# 10MHzRefOsc_2V1.net
KiCad netlist of a schematic drawn in EAGLE
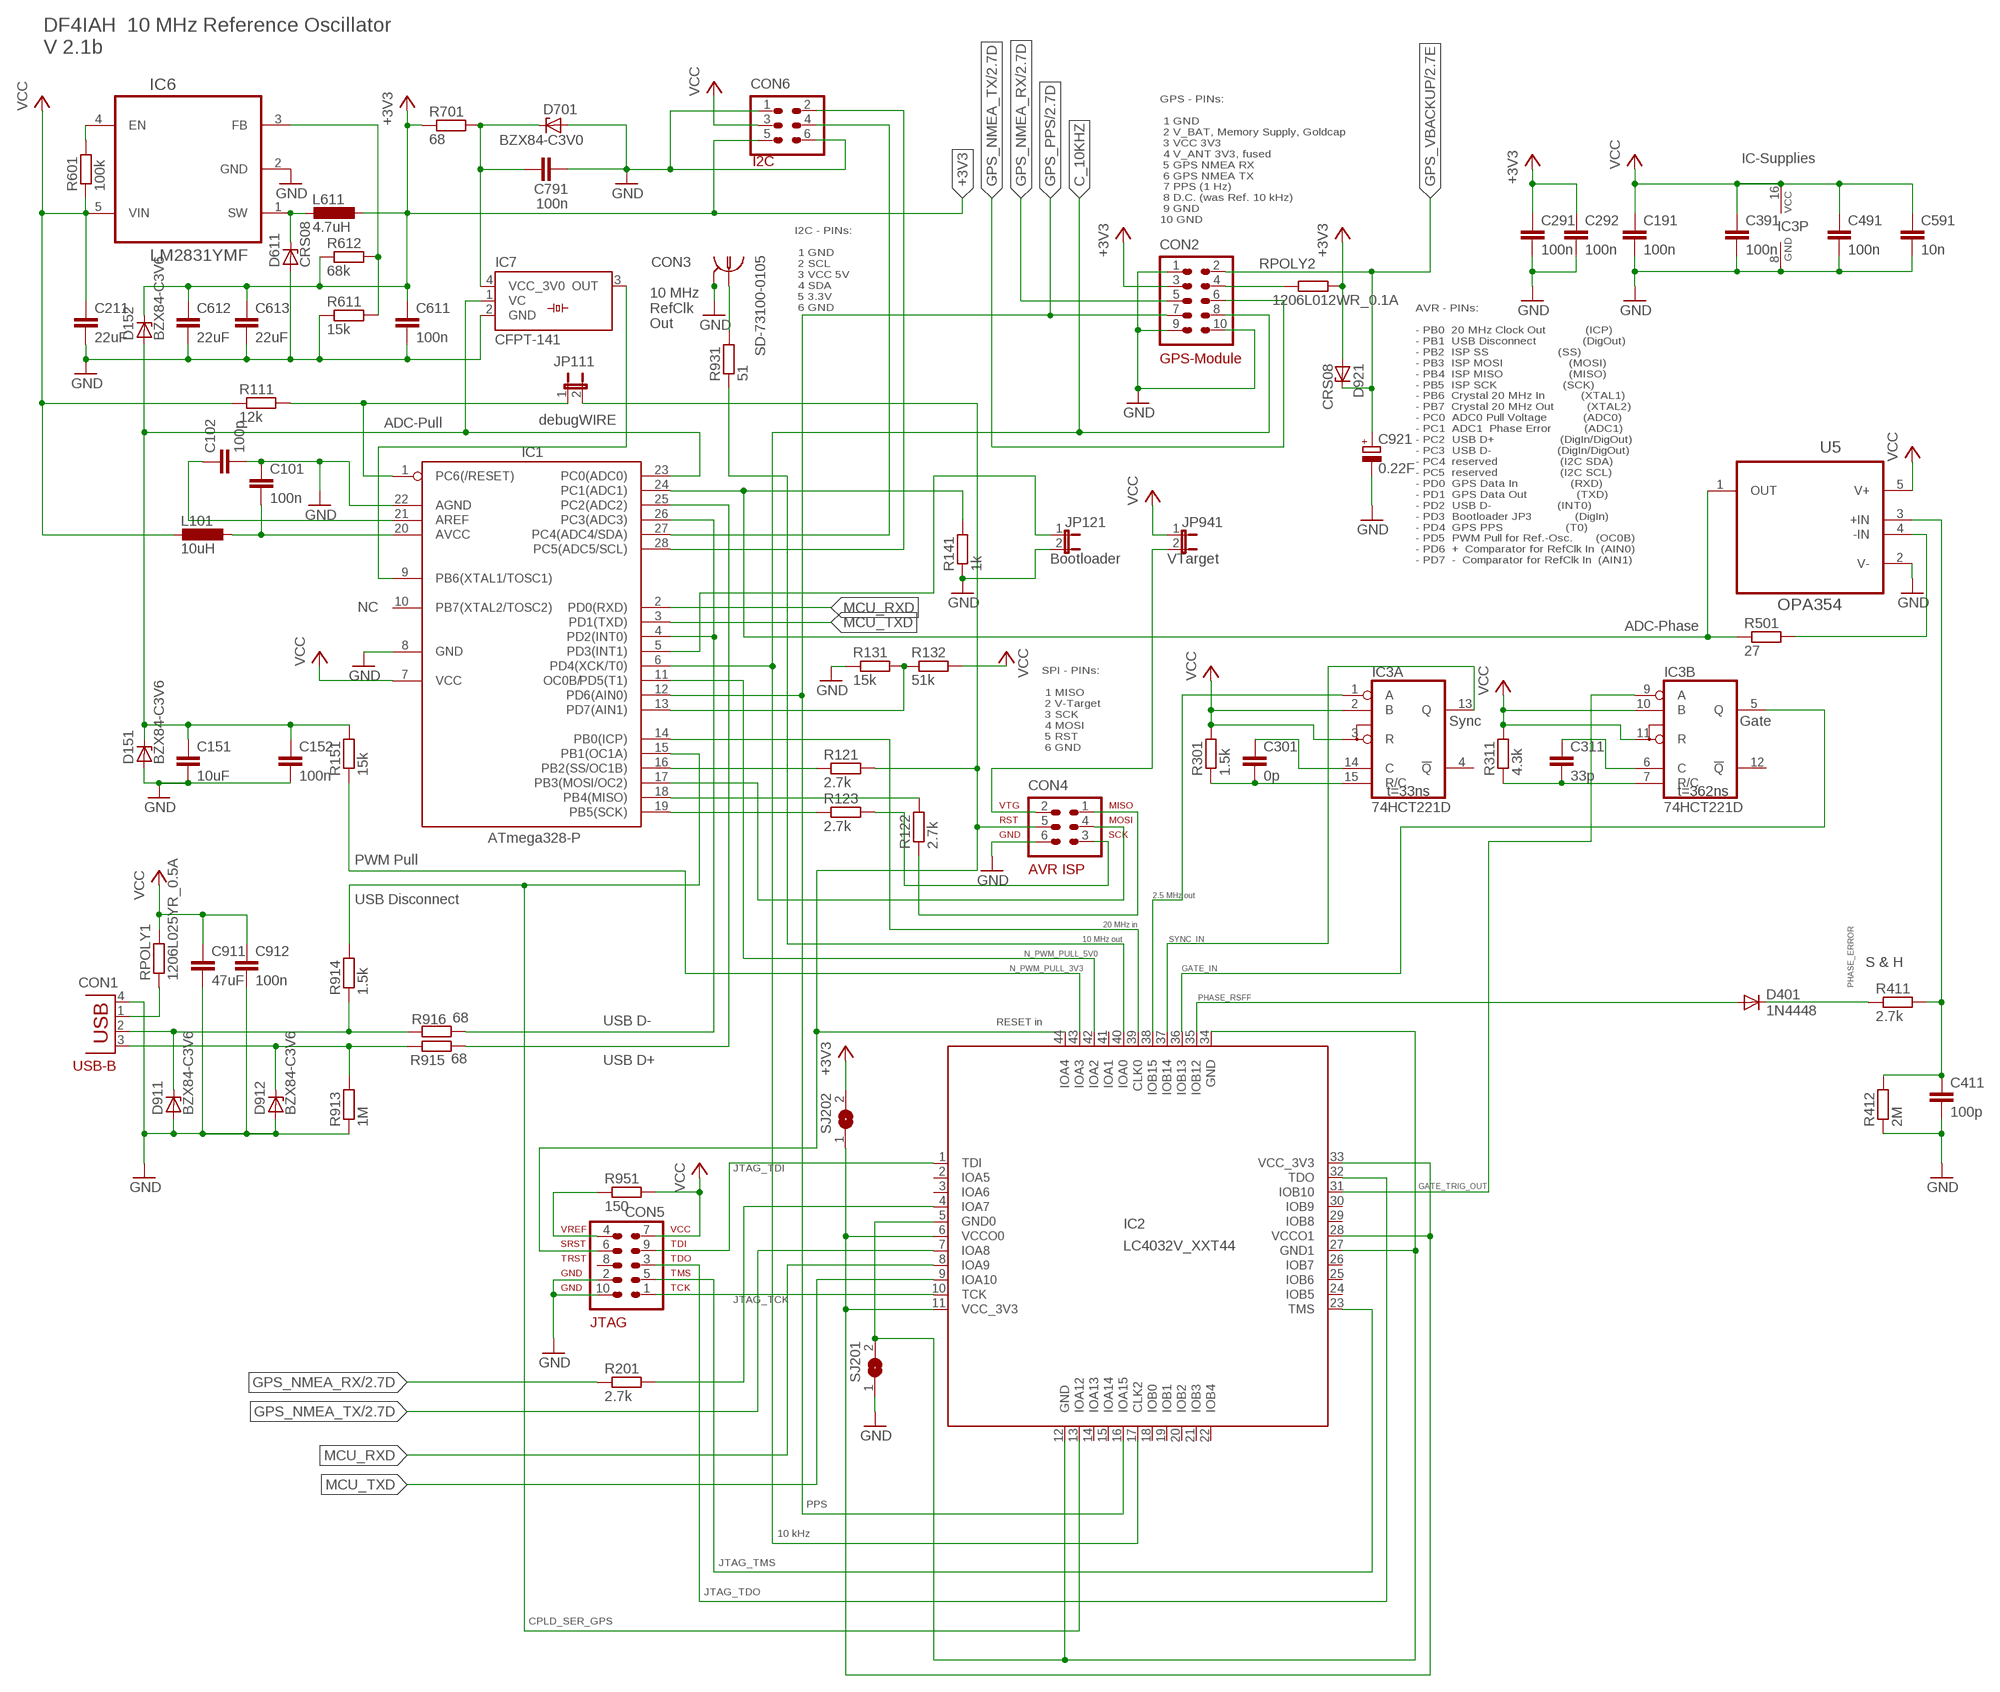
[diagram p0: schematic, sheet 1]
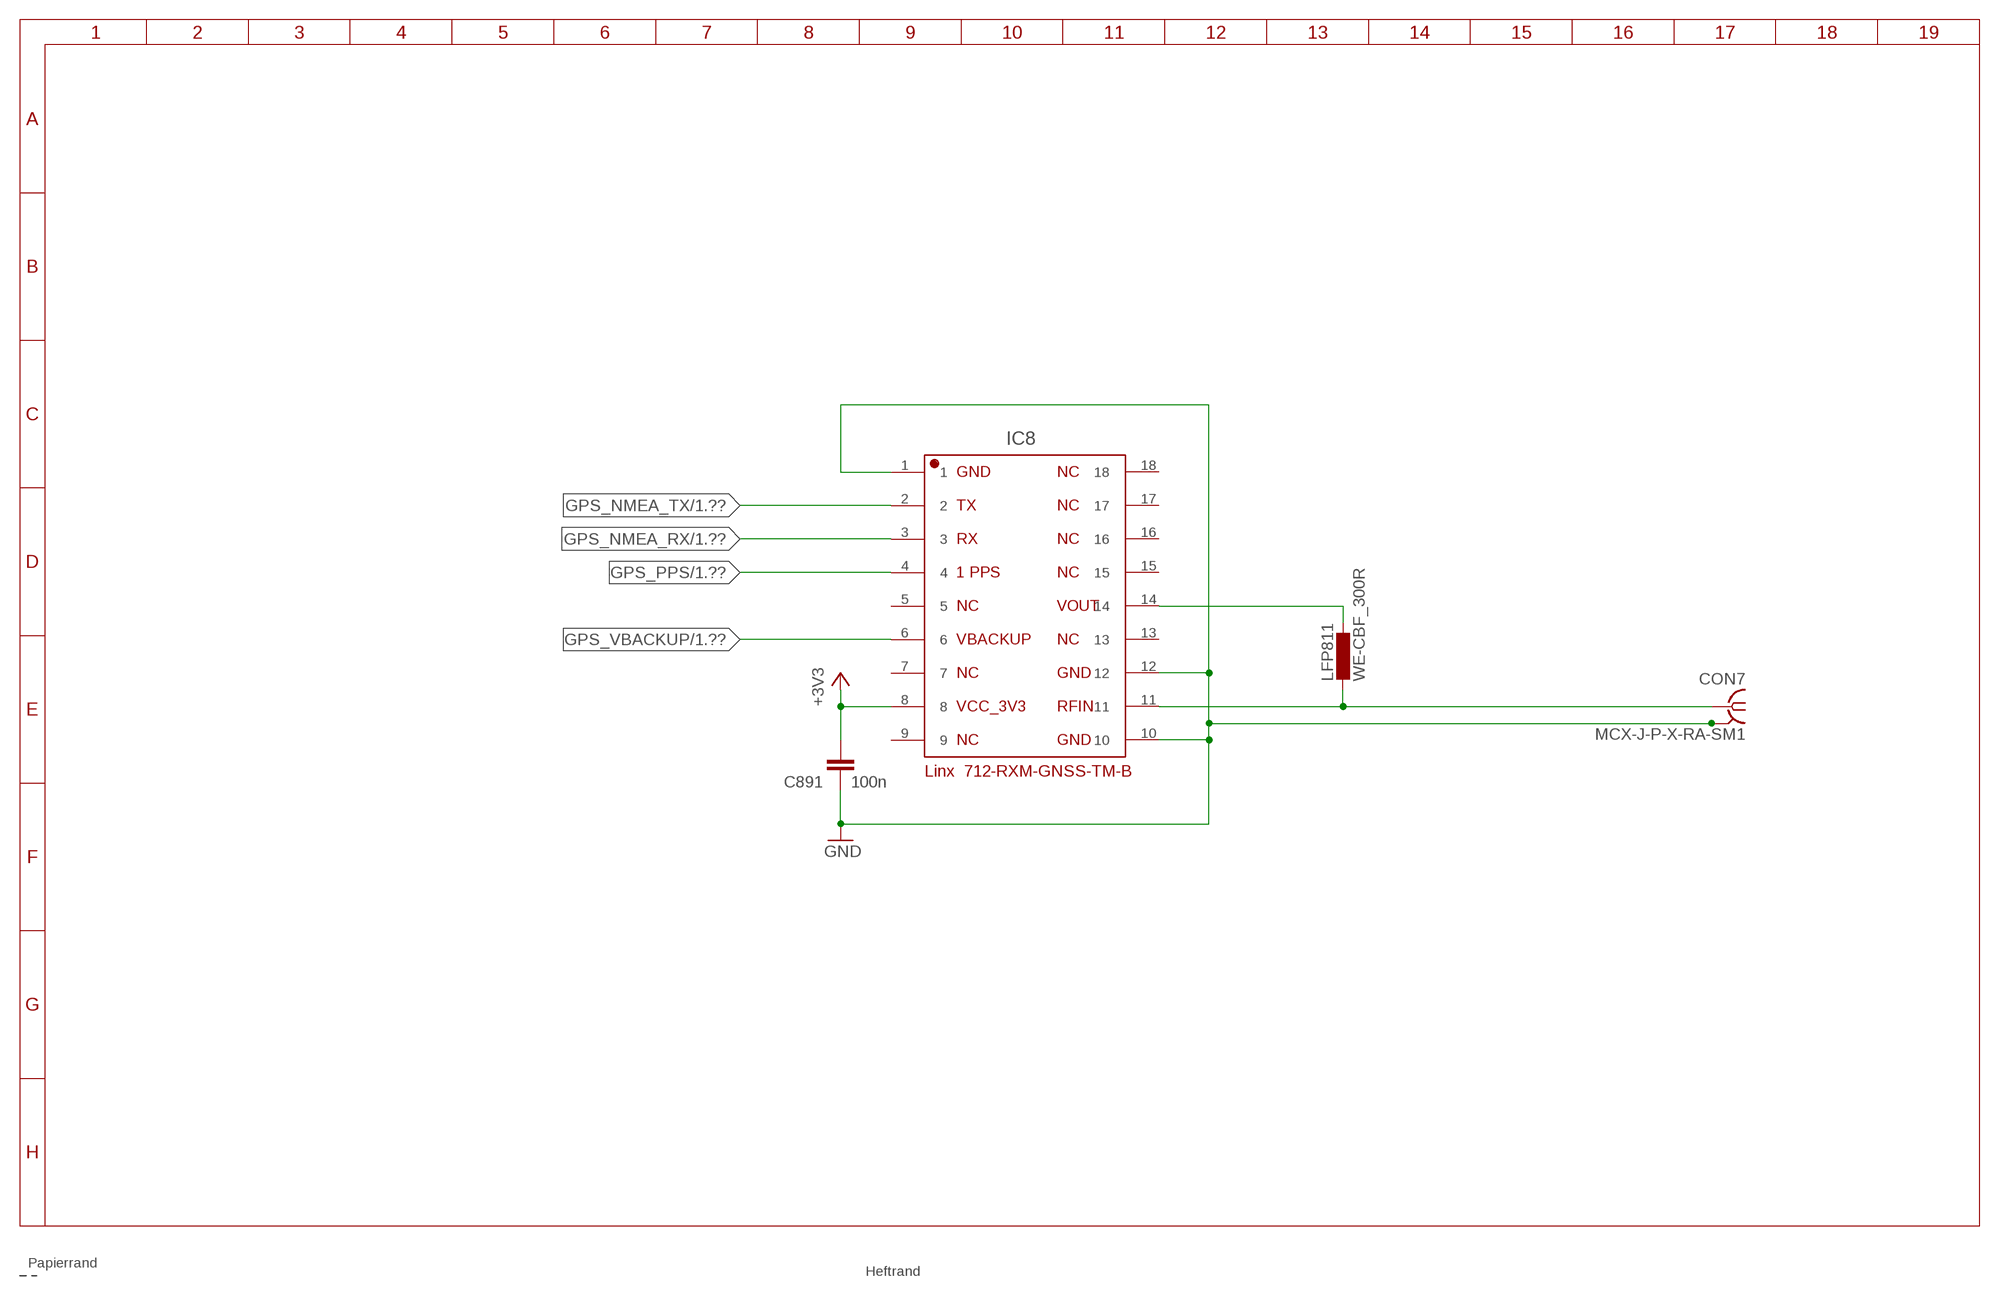
[diagram p1: schematic, sheet 2]
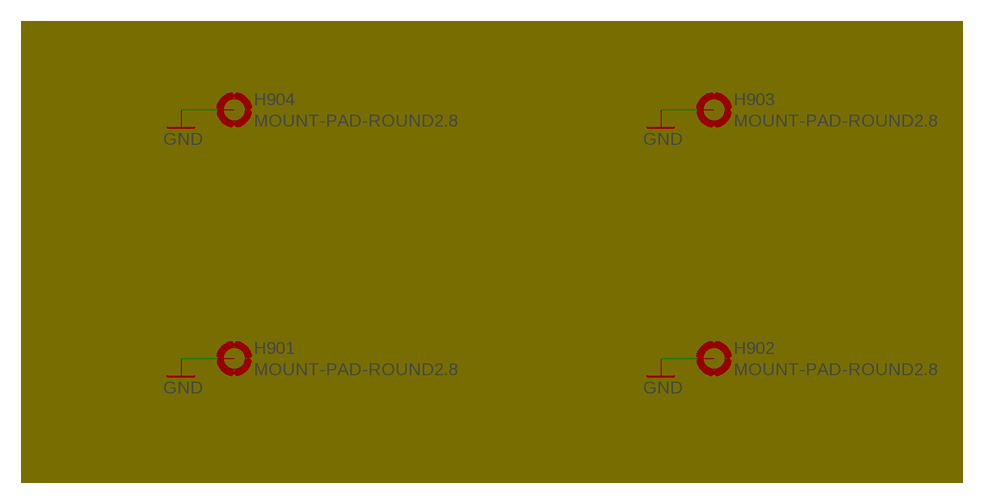
[diagram p2: schematic, sheet 3]

(export (version "E")
  (design (tool "Eeschema 10.0.6"))
  (components
    (comp (ref "C891")
      (value "100n")
      (footprint "eagle-import:C0805")
      (libsource (lib "eagle-import") (part "C-EUC0805"))
    )
    (comp (ref "CON7")
      (value "MCX-J-P-X-RA-SM1")
      (footprint "eagle-import:MCX-J-P-X-RA-SM1")
      (libsource (lib "eagle-import") (part "MCX-J-P-X-RA-SM1"))
    )
    (comp (ref "IC8")
      (value "712-RXM-GNSS-TM-B")
      (footprint "eagle-import:712-RXM-GNSS-TM-B")
      (libsource (lib "eagle-import") (part "712-RXM-GNSS-TM-B"))
    )
    (comp (ref "LFP811")
      (value "WE-CBF_300R")
      (footprint "eagle-import:L3216C")
      (libsource (lib "eagle-import") (part "L-EUL3216C"))
    )
    (comp (ref "C101")
      (value "100n")
      (footprint "eagle-import:C0805")
      (libsource (lib "eagle-import") (part "rcl_C-EUC0805"))
    )
    (comp (ref "C102")
      (value "100p")
      (footprint "eagle-import:C0805")
      (libsource (lib "eagle-import") (part "rcl_C-EUC0805"))
    )
    (comp (ref "C151")
      (value "10uF")
      (footprint "eagle-import:C0805")
      (libsource (lib "eagle-import") (part "rcl_C-EUC0805"))
    )
    (comp (ref "C152")
      (value "100n")
      (footprint "eagle-import:C0805")
      (libsource (lib "eagle-import") (part "rcl_C-EUC0805"))
    )
    (comp (ref "C191")
      (value "100n")
      (footprint "eagle-import:C0805")
      (libsource (lib "eagle-import") (part "rcl_C-EUC0805"))
    )
    (comp (ref "C211")
      (value "22uF")
      (footprint "eagle-import:C0805")
      (libsource (lib "eagle-import") (part "rcl_C-EUC0805"))
    )
    (comp (ref "C291")
      (value "100n")
      (footprint "eagle-import:C0805")
      (libsource (lib "eagle-import") (part "rcl_C-EUC0805"))
    )
    (comp (ref "C292")
      (value "100n")
      (footprint "eagle-import:C0805")
      (libsource (lib "eagle-import") (part "rcl_C-EUC0805"))
    )
    (comp (ref "C301")
      (value "0p")
      (footprint "eagle-import:C0805")
      (libsource (lib "eagle-import") (part "rcl_C-EUC0805"))
    )
    (comp (ref "C311")
      (value "33p")
      (footprint "eagle-import:C0805")
      (libsource (lib "eagle-import") (part "rcl_C-EUC0805"))
    )
    (comp (ref "C391")
      (value "100n")
      (footprint "eagle-import:C0805")
      (libsource (lib "eagle-import") (part "rcl_C-EUC0805"))
    )
    (comp (ref "C411")
      (value "100p")
      (footprint "eagle-import:C0805")
      (libsource (lib "eagle-import") (part "rcl_C-EUC0805"))
    )
    (comp (ref "C491")
      (value "100n")
      (footprint "eagle-import:C0805")
      (libsource (lib "eagle-import") (part "rcl_C-EUC0805"))
    )
    (comp (ref "C591")
      (value "10n")
      (footprint "eagle-import:C0805")
      (libsource (lib "eagle-import") (part "rcl_C-EUC0805"))
    )
    (comp (ref "C611")
      (value "100n")
      (footprint "eagle-import:C0805")
      (libsource (lib "eagle-import") (part "rcl_C-EUC0805"))
    )
    (comp (ref "C612")
      (value "22uF")
      (footprint "eagle-import:C0805")
      (libsource (lib "eagle-import") (part "rcl_C-EUC0805"))
    )
    (comp (ref "C613")
      (value "22uF")
      (footprint "eagle-import:C0805")
      (libsource (lib "eagle-import") (part "rcl_C-EUC0805"))
    )
    (comp (ref "C791")
      (value "100n")
      (footprint "eagle-import:C0805")
      (libsource (lib "eagle-import") (part "rcl_C-EUC0805"))
    )
    (comp (ref "C911")
      (value "47uF")
      (footprint "eagle-import:C0805")
      (libsource (lib "eagle-import") (part "rcl_C-EUC0805"))
    )
    (comp (ref "C912")
      (value "100n")
      (footprint "eagle-import:C0805")
      (libsource (lib "eagle-import") (part "rcl_C-EUC0805"))
    )
    (comp (ref "C921")
      (value "0.22F")
      (footprint "eagle-import:140CLH-1010")
      (libsource (lib "eagle-import") (part "CPOL-EU140CLH-1010"))
    )
    (comp (ref "CON1")
      (value "TYCO-AMP_USBUSB-B_SMT")
      (footprint "eagle-import:TYCO-AMP_USB-B_SMT")
      (fields (field (name "MF") "TYCO-AMP") (field (name "MPN") "1734346"))
      (libsource (lib "eagle-import") (part "TYCO-AMP_USBUSB-B_SMT"))
    )
    (comp (ref "CON2")
      (value "HEADER-2X5SMD")
      (footprint "eagle-import:2X5SMD")
      (libsource (lib "eagle-import") (part "HEADER-2X5SMD"))
    )
    (comp (ref "CON3")
      (value "SD-73100-0105")
      (footprint "eagle-import:MOLEX_BNC-JACK-50R_SD-73100-0105")
      (fields (field (name "MF") "MOLEX"))
      (libsource (lib "eagle-import") (part "MOLEX_BNC-JACK-50R_SD-73100-0105"))
    )
    (comp (ref "CON4")
      (value "AVR-ISP-6SMD")
      (footprint "eagle-import:2X3SMD")
      (libsource (lib "eagle-import") (part "AVR-ISP-6SMD"))
    )
    (comp (ref "CON5")
      (value "AVR-JTAG-10SMD")
      (footprint "eagle-import:2X5SMD")
      (libsource (lib "eagle-import") (part "AVR-JTAG-10SMD"))
    )
    (comp (ref "CON6")
      (value "HEADER-2X3SMD")
      (footprint "eagle-import:2X03SMD")
      (libsource (lib "eagle-import") (part "HEADER-2X3SMD"))
    )
    (comp (ref "D151")
      (value "BZX84-C3V6")
      (footprint "eagle-import:TO236")
      (libsource (lib "eagle-import") (part "BZX84CSMD"))
    )
    (comp (ref "D152")
      (value "BZX84-C3V6")
      (footprint "eagle-import:TO236")
      (libsource (lib "eagle-import") (part "BZX84CSMD"))
    )
    (comp (ref "D401")
      (value "1N4448")
      (footprint "eagle-import:SOD123")
      (libsource (lib "eagle-import") (part "DIODE-SOD123"))
    )
    (comp (ref "D611")
      (value "CRS08")
      (footprint "eagle-import:SOD80C")
      (libsource (lib "eagle-import") (part "ZENER-DIODESOD80C"))
    )
    (comp (ref "D701")
      (value "BZX84-C3V0")
      (footprint "eagle-import:TO236")
      (libsource (lib "eagle-import") (part "BZX84CSMD"))
    )
    (comp (ref "D911")
      (value "BZX84-C3V6")
      (footprint "eagle-import:TO236")
      (libsource (lib "eagle-import") (part "BZX84CSMD"))
    )
    (comp (ref "D912")
      (value "BZX84-C3V6")
      (footprint "eagle-import:TO236")
      (libsource (lib "eagle-import") (part "BZX84CSMD"))
    )
    (comp (ref "D921")
      (value "CRS08")
      (footprint "eagle-import:SOD80C")
      (libsource (lib "eagle-import") (part "ZENER-DIODESOD80C"))
    )
    (comp (ref "IC1")
      (value "ATmega328-P")
      (footprint "eagle-import:DIL28-3")
      (libsource (lib "eagle-import") (part "MEGA8-P"))
    )
    (comp (ref "IC2")
      (value "LC4032V_XXT44")
      (footprint "eagle-import:TQFP44")
      (libsource (lib "eagle-import") (part "LC4032V_XXT44"))
    )
    (comp (ref "IC3")
      (value "74HCT221D")
      (footprint "eagle-import:SO16")
      (libsource (lib "eagle-import") (part "74221DHCT"))
    )
    (comp (ref "IC6")
      (value "LM2831YMF")
      (footprint "eagle-import:SOT95P280X145-5N")
      (fields (field (name "MPN") "LM2831YMF/NOPB"))
      (libsource (lib "eagle-import") (part "LM2831YMF"))
    )
    (comp (ref "IC7")
      (value "CFPT-141")
      (footprint "eagle-import:CFPT-141")
      (fields (field (name "MF") "IQD-FREQUENCY-PRODUCTS") (field (name "MPN") "LFTVXO022175"))
      (libsource (lib "eagle-import") (part "CFPT-141"))
    )
    (comp (ref "JP111")
      (value "JP1E")
      (footprint "eagle-import:JP1")
      (libsource (lib "eagle-import") (part "JP1E"))
    )
    (comp (ref "JP121")
      (value "JP1E")
      (footprint "eagle-import:JP1")
      (libsource (lib "eagle-import") (part "JP1E"))
    )
    (comp (ref "JP941")
      (value "JP1E")
      (footprint "eagle-import:JP1")
      (libsource (lib "eagle-import") (part "JP1E"))
    )
    (comp (ref "L101")
      (value "10uH")
      (footprint "eagle-import:L1812")
      (libsource (lib "eagle-import") (part "rcl_L-EUL1812"))
    )
    (comp (ref "L611")
      (value "4.7uH")
      (footprint "eagle-import:L5650M")
      (libsource (lib "eagle-import") (part "rcl_L-EUL5650M"))
    )
    (comp (ref "R111")
      (value "12k")
      (footprint "eagle-import:R0805")
      (libsource (lib "eagle-import") (part "R-EU_R0805"))
    )
    (comp (ref "R121")
      (value "2.7k")
      (footprint "eagle-import:R0805")
      (libsource (lib "eagle-import") (part "R-EU_R0805"))
    )
    (comp (ref "R122")
      (value "2.7k")
      (footprint "eagle-import:R0805")
      (libsource (lib "eagle-import") (part "R-EU_R0805"))
    )
    (comp (ref "R123")
      (value "2.7k")
      (footprint "eagle-import:R0805")
      (libsource (lib "eagle-import") (part "R-EU_R0805"))
    )
    (comp (ref "R131")
      (value "15k")
      (footprint "eagle-import:R0805")
      (libsource (lib "eagle-import") (part "R-EU_R0805"))
    )
    (comp (ref "R132")
      (value "51k")
      (footprint "eagle-import:R0805")
      (libsource (lib "eagle-import") (part "R-EU_R0805"))
    )
    (comp (ref "R141")
      (value "1k")
      (footprint "eagle-import:R0805")
      (libsource (lib "eagle-import") (part "R-EU_R0805"))
    )
    (comp (ref "R151")
      (value "15k")
      (footprint "eagle-import:R0805")
      (libsource (lib "eagle-import") (part "R-EU_R0805"))
    )
    (comp (ref "R201")
      (value "2.7k")
      (footprint "eagle-import:R0805")
      (libsource (lib "eagle-import") (part "R-EU_R0805"))
    )
    (comp (ref "R301")
      (value "1.5k")
      (footprint "eagle-import:R0805")
      (libsource (lib "eagle-import") (part "R-EU_R0805"))
    )
    (comp (ref "R311")
      (value "4.3k")
      (footprint "eagle-import:R0805")
      (libsource (lib "eagle-import") (part "R-EU_R0805"))
    )
    (comp (ref "R411")
      (value "2.7k")
      (footprint "eagle-import:R0805")
      (libsource (lib "eagle-import") (part "R-EU_R0805"))
    )
    (comp (ref "R412")
      (value "2M")
      (footprint "eagle-import:R0805")
      (libsource (lib "eagle-import") (part "R-EU_R0805"))
    )
    (comp (ref "R501")
      (value "27")
      (footprint "eagle-import:R0805")
      (libsource (lib "eagle-import") (part "R-EU_R0805"))
    )
    (comp (ref "R601")
      (value "100k")
      (footprint "eagle-import:R0805")
      (libsource (lib "eagle-import") (part "R-EU_R0805"))
    )
    (comp (ref "R611")
      (value "15k")
      (footprint "eagle-import:R0805")
      (libsource (lib "eagle-import") (part "R-EU_R0805"))
    )
    (comp (ref "R612")
      (value "68k")
      (footprint "eagle-import:R0805")
      (libsource (lib "eagle-import") (part "R-EU_R0805"))
    )
    (comp (ref "R701")
      (value "68")
      (footprint "eagle-import:R0805")
      (libsource (lib "eagle-import") (part "R-EU_R0805"))
    )
    (comp (ref "R913")
      (value "1M")
      (footprint "eagle-import:R0805")
      (libsource (lib "eagle-import") (part "R-EU_R0805"))
    )
    (comp (ref "R914")
      (value "1.5k")
      (footprint "eagle-import:R0805")
      (libsource (lib "eagle-import") (part "R-EU_R0805"))
    )
    (comp (ref "R915")
      (value "68")
      (footprint "eagle-import:R0805")
      (libsource (lib "eagle-import") (part "R-EU_R0805"))
    )
    (comp (ref "R916")
      (value "68")
      (footprint "eagle-import:R0805")
      (libsource (lib "eagle-import") (part "R-EU_R0805"))
    )
    (comp (ref "R931")
      (value "51")
      (footprint "eagle-import:R0805")
      (libsource (lib "eagle-import") (part "R-EU_R0805"))
    )
    (comp (ref "R951")
      (value "150")
      (footprint "eagle-import:R0805")
      (libsource (lib "eagle-import") (part "R-EU_R0805"))
    )
    (comp (ref "RPOLY1")
      (value "1206L025YR_0.5A")
      (footprint "eagle-import:M1206")
      (libsource (lib "eagle-import") (part "R-EU_M1206"))
    )
    (comp (ref "RPOLY2")
      (value "1206L012WR_0.1A")
      (footprint "eagle-import:M1206")
      (libsource (lib "eagle-import") (part "R-EU_M1206"))
    )
    (comp (ref "SJ201")
      (value "SJ")
      (footprint "eagle-import:SJ")
      (libsource (lib "eagle-import") (part "SJ"))
    )
    (comp (ref "SJ202")
      (value "SJ")
      (footprint "eagle-import:SJ")
      (libsource (lib "eagle-import") (part "SJ"))
    )
    (comp (ref "U5")
      (value "OPA354")
      (footprint "eagle-import:SOT-23-5")
      (fields (field (name "MPN") "OPA354AIDBVT"))
      (libsource (lib "eagle-import") (part "OPA354"))
    )
    (comp (ref "H901")
      (value "MOUNT-PAD-ROUND2.8")
      (footprint "eagle-import:2,8-PAD")
      (libsource (lib "eagle-import") (part "MOUNT-PAD-ROUND2.8"))
    )
    (comp (ref "H902")
      (value "MOUNT-PAD-ROUND2.8")
      (footprint "eagle-import:2,8-PAD")
      (libsource (lib "eagle-import") (part "MOUNT-PAD-ROUND2.8"))
    )
    (comp (ref "H903")
      (value "MOUNT-PAD-ROUND2.8")
      (footprint "eagle-import:2,8-PAD")
      (libsource (lib "eagle-import") (part "MOUNT-PAD-ROUND2.8"))
    )
    (comp (ref "H904")
      (value "MOUNT-PAD-ROUND2.8")
      (footprint "eagle-import:2,8-PAD")
      (libsource (lib "eagle-import") (part "MOUNT-PAD-ROUND2.8"))
    )
  )
  (nets
    (net (code "1") (name "+3V3") (class "Default")
      (node (ref "C291") (pin "1") (pinfunction "1_1") (pintype "passive"))
      (node (ref "C292") (pin "1") (pinfunction "1_1") (pintype "passive"))
      (node (ref "C611") (pin "1") (pinfunction "1_1") (pintype "passive"))
      (node (ref "C612") (pin "1") (pinfunction "1_1") (pintype "passive"))
      (node (ref "C613") (pin "1") (pinfunction "1_1") (pintype "passive"))
      (node (ref "C891") (pin "1") (pinfunction "1_1") (pintype "passive"))
      (node (ref "CON2") (pin "3") (pinfunction "3_3") (pintype "passive"))
      (node (ref "CON6") (pin "5") (pinfunction "5_5") (pintype "passive"))
      (node (ref "D152") (pin "C") (pinfunction "C_C") (pintype "passive"))
      (node (ref "D921") (pin "A") (pinfunction "A_A") (pintype "passive"))
      (node (ref "IC8") (pin "8") (pinfunction "8_8") (pintype "power_in"))
      (node (ref "L611") (pin "1") (pinfunction "1_1") (pintype "passive"))
      (node (ref "R612") (pin "1") (pinfunction "1_1") (pintype "passive"))
      (node (ref "R701") (pin "1") (pinfunction "1_1") (pintype "passive"))
      (node (ref "RPOLY2") (pin "2") (pinfunction "2_2") (pintype "passive"))
      (node (ref "SJ202") (pin "2") (pinfunction "2_2") (pintype "passive"))
    )
    (net (code "2") (name "C_10KHZ") (class "Default")
      (node (ref "CON2") (pin "8") (pinfunction "8_8") (pintype "passive"))
      (node (ref "IC1") (pin "6") (pinfunction "PD4(XCK/T0)_6") (pintype "bidirectional"))
      (node (ref "IC2") (pin "17") (pinfunction "CLK2_17") (pintype "input"))
    )
    (net (code "3") (name "GATE_IN") (class "Default")
      (node (ref "IC2") (pin "36") (pinfunction "IOB13_36") (pintype "bidirectional"))
      (node (ref "IC3") (pin "5") (pinfunction "Q_5") (pintype "output"))
    )
    (net (code "4") (name "GATE_TRIG_OUT") (class "Default")
      (node (ref "IC2") (pin "31") (pinfunction "IOB10_31") (pintype "bidirectional"))
      (node (ref "IC3") (pin "9") (pinfunction "A_9") (pintype "input"))
    )
    (net (code "5") (name "GND") (class "Default")
      (node (ref "C101") (pin "1") (pinfunction "1_1") (pintype "passive"))
      (node (ref "C102") (pin "2") (pinfunction "2_2") (pintype "passive"))
      (node (ref "C151") (pin "2") (pinfunction "2_2") (pintype "passive"))
      (node (ref "C152") (pin "2") (pinfunction "2_2") (pintype "passive"))
      (node (ref "C191") (pin "2") (pinfunction "2_2") (pintype "passive"))
      (node (ref "C211") (pin "2") (pinfunction "2_2") (pintype "passive"))
      (node (ref "C291") (pin "2") (pinfunction "2_2") (pintype "passive"))
      (node (ref "C292") (pin "2") (pinfunction "2_2") (pintype "passive"))
      (node (ref "C391") (pin "2") (pinfunction "2_2") (pintype "passive"))
      (node (ref "C411") (pin "2") (pinfunction "2_2") (pintype "passive"))
      (node (ref "C491") (pin "2") (pinfunction "2_2") (pintype "passive"))
      (node (ref "C591") (pin "2") (pinfunction "2_2") (pintype "passive"))
      (node (ref "C611") (pin "2") (pinfunction "2_2") (pintype "passive"))
      (node (ref "C612") (pin "2") (pinfunction "2_2") (pintype "passive"))
      (node (ref "C613") (pin "2") (pinfunction "2_2") (pintype "passive"))
      (node (ref "C791") (pin "2") (pinfunction "2_2") (pintype "passive"))
      (node (ref "C891") (pin "2") (pinfunction "2_2") (pintype "passive"))
      (node (ref "C911") (pin "2") (pinfunction "2_2") (pintype "passive"))
      (node (ref "C912") (pin "2") (pinfunction "2_2") (pintype "passive"))
      (node (ref "C921") (pin "-") (pinfunction "-_-") (pintype "passive"))
      (node (ref "CON1") (pin "4") (pinfunction "GND_4") (pintype "bidirectional"))
      (node (ref "CON2") (pin "1") (pinfunction "1_1") (pintype "passive"))
      (node (ref "CON2") (pin "10") (pinfunction "10_10") (pintype "passive"))
      (node (ref "CON2") (pin "9") (pinfunction "9_9") (pintype "passive"))
      (node (ref "CON3") (pin "2") (pinfunction "2_2") (pintype "passive"))
      (node (ref "CON3") (pin "3") (pinfunction "3_3") (pintype "passive"))
      (node (ref "CON4") (pin "6") (pinfunction "6_6") (pintype "passive"))
      (node (ref "CON5") (pin "10") (pinfunction "10_10") (pintype "passive"))
      (node (ref "CON5") (pin "2") (pinfunction "2_2") (pintype "passive"))
      (node (ref "CON6") (pin "1") (pinfunction "1_1") (pintype "passive"))
      (node (ref "CON6") (pin "6") (pinfunction "6_6") (pintype "passive"))
      (node (ref "CON7") (pin "2") (pinfunction "2_2") (pintype "passive"))
      (node (ref "CON7") (pin "3") (pinfunction "3_3") (pintype "passive"))
      (node (ref "CON7") (pin "4") (pinfunction "4_4") (pintype "passive"))
      (node (ref "CON7") (pin "5") (pinfunction "5_5") (pintype "passive"))
      (node (ref "D151") (pin "A") (pinfunction "A_A") (pintype "passive"))
      (node (ref "D611") (pin "A") (pinfunction "A_A") (pintype "passive"))
      (node (ref "D701") (pin "A") (pinfunction "A_A") (pintype "passive"))
      (node (ref "D911") (pin "A") (pinfunction "A_A") (pintype "passive"))
      (node (ref "D912") (pin "A") (pinfunction "A_A") (pintype "passive"))
      (node (ref "H901") (pin "B2,8") (pinfunction "MOUNT_B2,8") (pintype "passive"))
      (node (ref "H902") (pin "B2,8") (pinfunction "MOUNT_B2,8") (pintype "passive"))
      (node (ref "H903") (pin "B2,8") (pinfunction "MOUNT_B2,8") (pintype "passive"))
      (node (ref "H904") (pin "B2,8") (pinfunction "MOUNT_B2,8") (pintype "passive"))
      (node (ref "IC1") (pin "22") (pinfunction "AGND_22") (pintype "bidirectional"))
      (node (ref "IC1") (pin "8") (pinfunction "GND_8") (pintype "bidirectional"))
      (node (ref "IC3") (pin "8") (pinfunction "GND_8") (pintype "power_in"))
      (node (ref "IC6") (pin "2") (pinfunction "GND_2") (pintype "passive"))
      (node (ref "IC7") (pin "2") (pinfunction "GND_2") (pintype "power_in"))
      (node (ref "IC8") (pin "1") (pinfunction "1_1") (pintype "power_in"))
      (node (ref "IC8") (pin "10") (pinfunction "10_10") (pintype "power_in"))
      (node (ref "IC8") (pin "12") (pinfunction "12_12") (pintype "power_in"))
      (node (ref "JP121") (pin "2") (pinfunction "2_2") (pintype "passive"))
      (node (ref "R131") (pin "1") (pinfunction "1_1") (pintype "passive"))
      (node (ref "R141") (pin "1") (pinfunction "1_1") (pintype "passive"))
      (node (ref "R412") (pin "1") (pinfunction "1_1") (pintype "passive"))
      (node (ref "R611") (pin "1") (pinfunction "1_1") (pintype "passive"))
      (node (ref "R913") (pin "1") (pinfunction "1_1") (pintype "passive"))
      (node (ref "SJ201") (pin "1") (pinfunction "1_1") (pintype "passive"))
      (node (ref "U5") (pin "2") (pinfunction "V-_2") (pintype "power_in"))
    )
    (net (code "6") (name "GPS_NMEA_RX") (class "Default")
      (node (ref "CON2") (pin "5") (pinfunction "5_5") (pintype "passive"))
      (node (ref "IC8") (pin "3") (pinfunction "3_3") (pintype "output"))
      (node (ref "R201") (pin "1") (pinfunction "1_1") (pintype "passive"))
    )
    (net (code "7") (name "GPS_NMEA_TX") (class "Default")
      (node (ref "CON2") (pin "6") (pinfunction "6_6") (pintype "passive"))
      (node (ref "IC2") (pin "7") (pinfunction "IOA8_7") (pintype "bidirectional"))
      (node (ref "IC8") (pin "2") (pinfunction "2_2") (pintype "input"))
    )
    (net (code "8") (name "GPS_PPS") (class "Default")
      (node (ref "CON2") (pin "7") (pinfunction "7_7") (pintype "passive"))
      (node (ref "IC1") (pin "12") (pinfunction "PD6(AIN0)_12") (pintype "bidirectional"))
      (node (ref "IC2") (pin "16") (pinfunction "IOA15_16") (pintype "bidirectional"))
      (node (ref "IC8") (pin "4") (pinfunction "4_4") (pintype "output"))
    )
    (net (code "9") (name "GPS_VBACKUP") (class "Default")
      (node (ref "C921") (pin "+") (pinfunction "+_+") (pintype "passive"))
      (node (ref "CON2") (pin "2") (pinfunction "2_2") (pintype "passive"))
      (node (ref "D921") (pin "C") (pinfunction "C_C") (pintype "passive"))
      (node (ref "IC8") (pin "6") (pinfunction "6_6") (pintype "power_in"))
    )
    (net (code "10") (name "MCU_RXD") (class "Default")
      (node (ref "IC1") (pin "2") (pinfunction "PD0(RXD)_2") (pintype "bidirectional"))
      (node (ref "IC2") (pin "8") (pinfunction "IOA9_8") (pintype "bidirectional"))
    )
    (net (code "11") (name "MCU_TXD") (class "Default")
      (node (ref "IC1") (pin "3") (pinfunction "PD1(TXD)_3") (pintype "bidirectional"))
      (node (ref "IC2") (pin "9") (pinfunction "IOA10_9") (pintype "bidirectional"))
    )
    (net (code "12") (name "N_PWM_PULL_3V3") (class "Default")
      (node (ref "IC2") (pin "43") (pinfunction "IOA3_43") (pintype "bidirectional"))
      (node (ref "R151") (pin "1") (pinfunction "1_1") (pintype "passive"))
    )
    (net (code "13") (name "N_PWM_PULL_5V0") (class "Default")
      (node (ref "IC1") (pin "11") (pinfunction "PD5(T1)_11") (pintype "bidirectional"))
      (node (ref "IC2") (pin "42") (pinfunction "IOA2_42") (pintype "bidirectional"))
    )
    (net (code "14") (name "Net-(CON1-D+)") (class "Default")
      (node (ref "CON1") (pin "3") (pinfunction "D+_3") (pintype "bidirectional"))
      (node (ref "D912") (pin "C") (pinfunction "C_C") (pintype "passive"))
      (node (ref "R913") (pin "2") (pinfunction "2_2") (pintype "passive"))
      (node (ref "R915") (pin "1") (pinfunction "1_1") (pintype "passive"))
    )
    (net (code "15") (name "Net-(CON1-D-)") (class "Default")
      (node (ref "CON1") (pin "2") (pinfunction "D-_2") (pintype "bidirectional"))
      (node (ref "D911") (pin "C") (pinfunction "C_C") (pintype "passive"))
      (node (ref "R914") (pin "1") (pinfunction "1_1") (pintype "passive"))
      (node (ref "R916") (pin "1") (pinfunction "1_1") (pintype "passive"))
    )
    (net (code "16") (name "Net-(CON1-VBUS)") (class "Default")
      (node (ref "CON1") (pin "1") (pinfunction "VBUS_1") (pintype "bidirectional"))
      (node (ref "RPOLY1") (pin "1") (pinfunction "1_1") (pintype "passive"))
    )
    (net (code "17") (name "Net-(CON2-Pad4)") (class "Default")
      (node (ref "CON2") (pin "4") (pinfunction "4_4") (pintype "passive"))
      (node (ref "RPOLY2") (pin "1") (pinfunction "1_1") (pintype "passive"))
    )
    (net (code "18") (name "Net-(CON3-Pad1)") (class "Default")
      (node (ref "CON3") (pin "1") (pinfunction "1_1") (pintype "passive"))
      (node (ref "R931") (pin "2") (pinfunction "2_2") (pintype "passive"))
    )
    (net (code "19") (name "Net-(CON4-Pad1)") (class "Default")
      (node (ref "CON4") (pin "1") (pinfunction "1_1") (pintype "passive"))
      (node (ref "R122") (pin "1") (pinfunction "1_1") (pintype "passive"))
    )
    (net (code "20") (name "Net-(CON4-Pad2)") (class "Default")
      (node (ref "CON4") (pin "2") (pinfunction "2_2") (pintype "passive"))
      (node (ref "JP941") (pin "2") (pinfunction "2_2") (pintype "passive"))
    )
    (net (code "21") (name "Net-(CON4-Pad3)") (class "Default")
      (node (ref "CON4") (pin "3") (pinfunction "3_3") (pintype "passive"))
      (node (ref "R123") (pin "2") (pinfunction "2_2") (pintype "passive"))
    )
    (net (code "22") (name "Net-(CON5-Pad4)") (class "Default")
      (node (ref "CON5") (pin "4") (pinfunction "4_4") (pintype "passive"))
      (node (ref "R951") (pin "1") (pinfunction "1_1") (pintype "passive"))
    )
    (net (code "23") (name "Net-(CON7-Pad1)") (class "Default")
      (node (ref "CON7") (pin "1") (pinfunction "1_1") (pintype "passive"))
      (node (ref "IC8") (pin "11") (pinfunction "11_11") (pintype "input"))
      (node (ref "LFP811") (pin "2") (pinfunction "2_2") (pintype "passive"))
    )
    (net (code "24") (name "Net-(IC1-AREF)") (class "Default")
      (node (ref "C102") (pin "1") (pinfunction "1_1") (pintype "passive"))
      (node (ref "IC1") (pin "21") (pinfunction "AREF_21") (pintype "bidirectional"))
    )
    (net (code "25") (name "Net-(IC1-AVCC)") (class "Default")
      (node (ref "C101") (pin "2") (pinfunction "2_2") (pintype "passive"))
      (node (ref "IC1") (pin "20") (pinfunction "AVCC_20") (pintype "bidirectional"))
      (node (ref "L101") (pin "1") (pinfunction "1_1") (pintype "passive"))
    )
    (net (code "26") (name "Net-(IC1-PB0(ICP))") (class "Default")
      (node (ref "IC1") (pin "14") (pinfunction "PB0(ICP)_14") (pintype "bidirectional"))
      (node (ref "IC2") (pin "39") (pinfunction "CLK0_39") (pintype "input"))
    )
    (net (code "27") (name "Net-(IC1-PB1(OC1A))") (class "Default")
      (node (ref "IC1") (pin "15") (pinfunction "PB1(OC1A)_15") (pintype "bidirectional"))
      (node (ref "IC2") (pin "13") (pinfunction "IOA12_13") (pintype "bidirectional"))
      (node (ref "R914") (pin "2") (pinfunction "2_2") (pintype "passive"))
    )
    (net (code "28") (name "Net-(IC1-PB2(SS{slash}OC1B))") (class "Default")
      (node (ref "IC1") (pin "16") (pinfunction "PB2(SS/OC1B)_16") (pintype "bidirectional"))
      (node (ref "R121") (pin "1") (pinfunction "1_1") (pintype "passive"))
    )
    (net (code "29") (name "Net-(IC1-PB3(MOSI{slash}OC2))") (class "Default")
      (node (ref "CON4") (pin "4") (pinfunction "4_4") (pintype "passive"))
      (node (ref "IC1") (pin "17") (pinfunction "PB3(MOSI/OC2)_17") (pintype "bidirectional"))
    )
    (net (code "30") (name "Net-(IC1-PB4(MISO))") (class "Default")
      (node (ref "IC1") (pin "18") (pinfunction "PB4(MISO)_18") (pintype "bidirectional"))
      (node (ref "R122") (pin "2") (pinfunction "2_2") (pintype "passive"))
    )
    (net (code "31") (name "Net-(IC1-PB5(SCK))") (class "Default")
      (node (ref "IC1") (pin "19") (pinfunction "PB5(SCK)_19") (pintype "bidirectional"))
      (node (ref "R123") (pin "1") (pinfunction "1_1") (pintype "passive"))
    )
    (net (code "32") (name "Net-(IC1-PB6(XTAL1{slash}TOSC1))") (class "Default")
      (node (ref "IC1") (pin "9") (pinfunction "PB6(XTAL1/TOSC1)_9") (pintype "bidirectional"))
      (node (ref "IC7") (pin "3") (pinfunction "OUT_3") (pintype "output"))
    )
    (net (code "33") (name "Net-(IC1-PC0(ADC0))") (class "Default")
      (node (ref "C151") (pin "1") (pinfunction "1_1") (pintype "passive"))
      (node (ref "C152") (pin "1") (pinfunction "1_1") (pintype "passive"))
      (node (ref "D151") (pin "C") (pinfunction "C_C") (pintype "passive"))
      (node (ref "D152") (pin "A") (pinfunction "A_A") (pintype "passive"))
      (node (ref "IC1") (pin "23") (pinfunction "PC0(ADC0)_23") (pintype "bidirectional"))
      (node (ref "IC7") (pin "1") (pinfunction "VC_1") (pintype "input"))
      (node (ref "R151") (pin "2") (pinfunction "2_2") (pintype "passive"))
    )
    (net (code "34") (name "Net-(IC1-PC1(ADC1))") (class "Default")
      (node (ref "IC1") (pin "24") (pinfunction "PC1(ADC1)_24") (pintype "bidirectional"))
      (node (ref "R141") (pin "2") (pinfunction "2_2") (pintype "passive"))
      (node (ref "R501") (pin "1") (pinfunction "1_1") (pintype "passive"))
      (node (ref "U5") (pin "1") (pinfunction "OUT_1") (pintype "output"))
    )
    (net (code "35") (name "Net-(IC1-PC2(ADC2))") (class "Default")
      (node (ref "IC1") (pin "25") (pinfunction "PC2(ADC2)_25") (pintype "bidirectional"))
      (node (ref "R915") (pin "2") (pinfunction "2_2") (pintype "passive"))
    )
    (net (code "36") (name "Net-(IC1-PC3(ADC3))") (class "Default")
      (node (ref "IC1") (pin "26") (pinfunction "PC3(ADC3)_26") (pintype "bidirectional"))
      (node (ref "IC1") (pin "4") (pinfunction "PD2(INT0)_4") (pintype "bidirectional"))
      (node (ref "R916") (pin "2") (pinfunction "2_2") (pintype "passive"))
    )
    (net (code "37") (name "Net-(IC1-PC4(ADC4{slash}SDA))") (class "Default")
      (node (ref "CON6") (pin "4") (pinfunction "4_4") (pintype "passive"))
      (node (ref "IC1") (pin "27") (pinfunction "PC4(ADC4/SDA)_27") (pintype "bidirectional"))
    )
    (net (code "38") (name "Net-(IC1-PC5(ADC5{slash}SCL))") (class "Default")
      (node (ref "CON6") (pin "2") (pinfunction "2_2") (pintype "passive"))
      (node (ref "IC1") (pin "28") (pinfunction "PC5(ADC5/SCL)_28") (pintype "bidirectional"))
    )
    (net (code "39") (name "Net-(IC1-PC6({slash}RESET))") (class "Default")
      (node (ref "IC1") (pin "1") (pinfunction "PC6(/RESET)_1") (pintype "bidirectional"))
      (node (ref "JP111") (pin "1") (pinfunction "1_1") (pintype "passive"))
      (node (ref "R111") (pin "2") (pinfunction "2_2") (pintype "passive"))
    )
    (net (code "40") (name "Net-(IC1-PD3(INT1))") (class "Default")
      (node (ref "IC1") (pin "5") (pinfunction "PD3(INT1)_5") (pintype "bidirectional"))
      (node (ref "JP121") (pin "1") (pinfunction "1_1") (pintype "passive"))
    )
    (net (code "41") (name "Net-(IC1-PD7(AIN1))") (class "Default")
      (node (ref "IC1") (pin "13") (pinfunction "PD7(AIN1)_13") (pintype "bidirectional"))
      (node (ref "R131") (pin "2") (pinfunction "2_2") (pintype "passive"))
      (node (ref "R132") (pin "1") (pinfunction "1_1") (pintype "passive"))
    )
    (net (code "42") (name "Net-(IC2-GND0)") (class "Default")
      (node (ref "IC2") (pin "12") (pinfunction "GND_12") (pintype "power_in"))
      (node (ref "IC2") (pin "27") (pinfunction "GND1_27") (pintype "power_in"))
      (node (ref "IC2") (pin "34") (pinfunction "GND_34") (pintype "power_in"))
      (node (ref "IC2") (pin "5") (pinfunction "GND0_5") (pintype "power_in"))
      (node (ref "SJ201") (pin "2") (pinfunction "2_2") (pintype "passive"))
    )
    (net (code "43") (name "Net-(IC2-IOA0)") (class "Default")
      (node (ref "IC2") (pin "40") (pinfunction "IOA0_40") (pintype "bidirectional"))
      (node (ref "R931") (pin "1") (pinfunction "1_1") (pintype "passive"))
    )
    (net (code "44") (name "Net-(IC2-IOA4)") (class "Default")
      (node (ref "CON4") (pin "5") (pinfunction "5_5") (pintype "passive"))
      (node (ref "CON5") (pin "6") (pinfunction "6_6") (pintype "passive"))
      (node (ref "IC2") (pin "44") (pinfunction "IOA4_44") (pintype "bidirectional"))
      (node (ref "JP111") (pin "2") (pinfunction "2_2") (pintype "passive"))
      (node (ref "R121") (pin "2") (pinfunction "2_2") (pintype "passive"))
    )
    (net (code "45") (name "Net-(IC2-IOA7)") (class "Default")
      (node (ref "IC2") (pin "4") (pinfunction "IOA7_4") (pintype "bidirectional"))
      (node (ref "R201") (pin "2") (pinfunction "2_2") (pintype "passive"))
    )
    (net (code "46") (name "Net-(IC2-IOB15)") (class "Default")
      (node (ref "IC2") (pin "38") (pinfunction "IOB15_38") (pintype "bidirectional"))
      (node (ref "IC3") (pin "1") (pinfunction "A_1") (pintype "input"))
    )
    (net (code "47") (name "Net-(IC2-TCK)") (class "Default")
      (node (ref "CON5") (pin "1") (pinfunction "1_1") (pintype "passive"))
      (node (ref "IC2") (pin "10") (pinfunction "TCK_10") (pintype "input"))
    )
    (net (code "48") (name "Net-(IC2-TDI)") (class "Default")
      (node (ref "CON5") (pin "9") (pinfunction "9_9") (pintype "passive"))
      (node (ref "IC2") (pin "1") (pinfunction "TDI_1") (pintype "input"))
    )
    (net (code "49") (name "Net-(IC2-TDO)") (class "Default")
      (node (ref "CON5") (pin "3") (pinfunction "3_3") (pintype "passive"))
      (node (ref "IC2") (pin "32") (pinfunction "TDO_32") (pintype "output"))
    )
    (net (code "50") (name "Net-(IC2-TMS)") (class "Default")
      (node (ref "CON5") (pin "5") (pinfunction "5_5") (pintype "passive"))
      (node (ref "IC2") (pin "23") (pinfunction "TMS_23") (pintype "input"))
    )
    (net (code "51") (name "Net-(IC2-VCCO0)") (class "Default")
      (node (ref "IC2") (pin "11") (pinfunction "VCC_3V3_11") (pintype "power_in"))
      (node (ref "IC2") (pin "28") (pinfunction "VCCO1_28") (pintype "power_in"))
      (node (ref "IC2") (pin "33") (pinfunction "VCC_3V3_33") (pintype "power_in"))
      (node (ref "IC2") (pin "6") (pinfunction "VCCO0_6") (pintype "power_in"))
      (node (ref "SJ202") (pin "1") (pinfunction "1_1") (pintype "passive"))
    )
    (net (code "52") (name "Net-(IC3A-C)") (class "Default")
      (node (ref "C301") (pin "1") (pinfunction "1_1") (pintype "passive"))
      (node (ref "IC3") (pin "14") (pinfunction "C_14") (pintype "input"))
    )
    (net (code "53") (name "Net-(IC3A-R{slash}C)") (class "Default")
      (node (ref "C301") (pin "2") (pinfunction "2_2") (pintype "passive"))
      (node (ref "IC3") (pin "15") (pinfunction "R/C_15") (pintype "input"))
      (node (ref "R301") (pin "1") (pinfunction "1_1") (pintype "passive"))
    )
    (net (code "54") (name "Net-(IC3B-C)") (class "Default")
      (node (ref "C311") (pin "1") (pinfunction "1_1") (pintype "passive"))
      (node (ref "IC3") (pin "6") (pinfunction "C_6") (pintype "input"))
    )
    (net (code "55") (name "Net-(IC3B-R{slash}C)") (class "Default")
      (node (ref "C311") (pin "2") (pinfunction "2_2") (pintype "passive"))
      (node (ref "IC3") (pin "7") (pinfunction "R/C_7") (pintype "input"))
      (node (ref "R311") (pin "1") (pinfunction "1_1") (pintype "passive"))
    )
    (net (code "56") (name "Net-(IC6-EN)") (class "Default")
      (node (ref "IC6") (pin "4") (pinfunction "EN_4") (pintype "input"))
      (node (ref "R601") (pin "2") (pinfunction "2_2") (pintype "passive"))
    )
    (net (code "57") (name "Net-(IC6-FB)") (class "Default")
      (node (ref "IC6") (pin "3") (pinfunction "FB_3") (pintype "input"))
      (node (ref "R611") (pin "2") (pinfunction "2_2") (pintype "passive"))
      (node (ref "R612") (pin "2") (pinfunction "2_2") (pintype "passive"))
    )
    (net (code "58") (name "Net-(IC6-SW)") (class "Default")
      (node (ref "D611") (pin "C") (pinfunction "C_C") (pintype "passive"))
      (node (ref "IC6") (pin "1") (pinfunction "SW_1") (pintype "output"))
      (node (ref "L611") (pin "2") (pinfunction "2_2") (pintype "passive"))
    )
    (net (code "59") (name "Net-(IC7-VCC_3V0)") (class "Default")
      (node (ref "C791") (pin "1") (pinfunction "1_1") (pintype "passive"))
      (node (ref "D701") (pin "C") (pinfunction "C_C") (pintype "passive"))
      (node (ref "IC7") (pin "4") (pinfunction "VCC_3V0_4") (pintype "power_in"))
      (node (ref "R701") (pin "2") (pinfunction "2_2") (pintype "passive"))
    )
    (net (code "60") (name "Net-(IC8-Pad14)") (class "Default")
      (node (ref "IC8") (pin "14") (pinfunction "14_14") (pintype "power_in"))
      (node (ref "LFP811") (pin "1") (pinfunction "1_1") (pintype "passive"))
    )
    (net (code "61") (name "Net-(U5-+IN)") (class "Default")
      (node (ref "C411") (pin "1") (pinfunction "1_1") (pintype "passive"))
      (node (ref "R411") (pin "2") (pinfunction "2_2") (pintype "passive"))
      (node (ref "R412") (pin "2") (pinfunction "2_2") (pintype "passive"))
      (node (ref "U5") (pin "3") (pinfunction "+IN_3") (pintype "input"))
    )
    (net (code "62") (name "Net-(U5--IN)") (class "Default")
      (node (ref "R501") (pin "2") (pinfunction "2_2") (pintype "passive"))
      (node (ref "U5") (pin "4") (pinfunction "-IN_4") (pintype "input"))
    )
    (net (code "63") (name "PHASE_ERROR") (class "Default")
      (node (ref "D401") (pin "C") (pinfunction "C_C") (pintype "passive"))
      (node (ref "R411") (pin "1") (pinfunction "1_1") (pintype "passive"))
    )
    (net (code "64") (name "PHASE_RSFF") (class "Default")
      (node (ref "D401") (pin "A") (pinfunction "A_A") (pintype "passive"))
      (node (ref "IC2") (pin "35") (pinfunction "IOB12_35") (pintype "bidirectional"))
    )
    (net (code "65") (name "SYNC_IN") (class "Default")
      (node (ref "IC2") (pin "37") (pinfunction "IOB14_37") (pintype "bidirectional"))
      (node (ref "IC3") (pin "13") (pinfunction "Q_13") (pintype "output"))
    )
    (net (code "66") (name "VCC") (class "Default")
      (node (ref "C191") (pin "1") (pinfunction "1_1") (pintype "passive"))
      (node (ref "C211") (pin "1") (pinfunction "1_1") (pintype "passive"))
      (node (ref "C391") (pin "1") (pinfunction "1_1") (pintype "passive"))
      (node (ref "C491") (pin "1") (pinfunction "1_1") (pintype "passive"))
      (node (ref "C591") (pin "1") (pinfunction "1_1") (pintype "passive"))
      (node (ref "C911") (pin "1") (pinfunction "1_1") (pintype "passive"))
      (node (ref "C912") (pin "1") (pinfunction "1_1") (pintype "passive"))
      (node (ref "CON5") (pin "7") (pinfunction "7_7") (pintype "passive"))
      (node (ref "CON6") (pin "3") (pinfunction "3_3") (pintype "passive"))
      (node (ref "IC1") (pin "7") (pinfunction "VCC_7") (pintype "bidirectional"))
      (node (ref "IC3") (pin "10") (pinfunction "B_10") (pintype "input"))
      (node (ref "IC3") (pin "11") (pinfunction "R_11") (pintype "input"))
      (node (ref "IC3") (pin "16") (pinfunction "VCC_16") (pintype "power_in"))
      (node (ref "IC3") (pin "2") (pinfunction "B_2") (pintype "input"))
      (node (ref "IC3") (pin "3") (pinfunction "R_3") (pintype "input"))
      (node (ref "IC6") (pin "5") (pinfunction "VIN_5") (pintype "power_in"))
      (node (ref "JP941") (pin "1") (pinfunction "1_1") (pintype "passive"))
      (node (ref "L101") (pin "2") (pinfunction "2_2") (pintype "passive"))
      (node (ref "R111") (pin "1") (pinfunction "1_1") (pintype "passive"))
      (node (ref "R132") (pin "2") (pinfunction "2_2") (pintype "passive"))
      (node (ref "R301") (pin "2") (pinfunction "2_2") (pintype "passive"))
      (node (ref "R311") (pin "2") (pinfunction "2_2") (pintype "passive"))
      (node (ref "R601") (pin "1") (pinfunction "1_1") (pintype "passive"))
      (node (ref "R951") (pin "2") (pinfunction "2_2") (pintype "passive"))
      (node (ref "RPOLY1") (pin "2") (pinfunction "2_2") (pintype "passive"))
      (node (ref "U5") (pin "5") (pinfunction "V+_5") (pintype "power_in"))
    )
    (net (code "67") (name "unconnected-(CON5-Pad8)") (class "Default")
      (node (ref "CON5") (pin "8") (pinfunction "8_8") (pintype "passive"))
    )
    (net (code "68") (name "unconnected-(IC1-PB7(XTAL2{slash}TOSC2)-Pad10)") (class "Default")
      (node (ref "IC1") (pin "10") (pinfunction "PB7(XTAL2/TOSC2)_10") (pintype "bidirectional"))
    )
    (net (code "69") (name "unconnected-(IC2-IOA1-Pad41)") (class "Default")
      (node (ref "IC2") (pin "41") (pinfunction "IOA1_41") (pintype "bidirectional"))
    )
    (net (code "70") (name "unconnected-(IC2-IOA5-Pad2)") (class "Default")
      (node (ref "IC2") (pin "2") (pinfunction "IOA5_2") (pintype "bidirectional"))
    )
    (net (code "71") (name "unconnected-(IC2-IOA6-Pad3)") (class "Default")
      (node (ref "IC2") (pin "3") (pinfunction "IOA6_3") (pintype "bidirectional"))
    )
    (net (code "72") (name "unconnected-(IC2-IOA13-Pad14)") (class "Default")
      (node (ref "IC2") (pin "14") (pinfunction "IOA13_14") (pintype "bidirectional"))
    )
    (net (code "73") (name "unconnected-(IC2-IOA14-Pad15)") (class "Default")
      (node (ref "IC2") (pin "15") (pinfunction "IOA14_15") (pintype "bidirectional"))
    )
    (net (code "74") (name "unconnected-(IC2-IOB0-Pad18)") (class "Default")
      (node (ref "IC2") (pin "18") (pinfunction "IOB0_18") (pintype "bidirectional"))
    )
    (net (code "75") (name "unconnected-(IC2-IOB1-Pad19)") (class "Default")
      (node (ref "IC2") (pin "19") (pinfunction "IOB1_19") (pintype "bidirectional"))
    )
    (net (code "76") (name "unconnected-(IC2-IOB2-Pad20)") (class "Default")
      (node (ref "IC2") (pin "20") (pinfunction "IOB2_20") (pintype "bidirectional"))
    )
    (net (code "77") (name "unconnected-(IC2-IOB3-Pad21)") (class "Default")
      (node (ref "IC2") (pin "21") (pinfunction "IOB3_21") (pintype "bidirectional"))
    )
    (net (code "78") (name "unconnected-(IC2-IOB4-Pad22)") (class "Default")
      (node (ref "IC2") (pin "22") (pinfunction "IOB4_22") (pintype "bidirectional"))
    )
    (net (code "79") (name "unconnected-(IC2-IOB5-Pad24)") (class "Default")
      (node (ref "IC2") (pin "24") (pinfunction "IOB5_24") (pintype "bidirectional"))
    )
    (net (code "80") (name "unconnected-(IC2-IOB6-Pad25)") (class "Default")
      (node (ref "IC2") (pin "25") (pinfunction "IOB6_25") (pintype "bidirectional"))
    )
    (net (code "81") (name "unconnected-(IC2-IOB7-Pad26)") (class "Default")
      (node (ref "IC2") (pin "26") (pinfunction "IOB7_26") (pintype "bidirectional"))
    )
    (net (code "82") (name "unconnected-(IC2-IOB8-Pad29)") (class "Default")
      (node (ref "IC2") (pin "29") (pinfunction "IOB8_29") (pintype "bidirectional"))
    )
    (net (code "83") (name "unconnected-(IC2-IOB9-Pad30)") (class "Default")
      (node (ref "IC2") (pin "30") (pinfunction "IOB9_30") (pintype "bidirectional"))
    )
    (net (code "84") (name "unconnected-(IC3A-~{Q}-Pad4)") (class "Default")
      (node (ref "IC3") (pin "4") (pinfunction "~{Q}_4") (pintype "output"))
    )
    (net (code "85") (name "unconnected-(IC3B-~{Q}-Pad12)") (class "Default")
      (node (ref "IC3") (pin "12") (pinfunction "~{Q}_12") (pintype "output"))
    )
    (net (code "86") (name "unconnected-(IC8-Pad5)") (class "Default")
      (node (ref "IC8") (pin "5") (pinfunction "5_5") (pintype "no_connect"))
    )
    (net (code "87") (name "unconnected-(IC8-Pad7)") (class "Default")
      (node (ref "IC8") (pin "7") (pinfunction "7_7") (pintype "bidirectional"))
    )
    (net (code "88") (name "unconnected-(IC8-Pad9)") (class "Default")
      (node (ref "IC8") (pin "9") (pinfunction "9_9") (pintype "no_connect"))
    )
    (net (code "89") (name "unconnected-(IC8-Pad13)") (class "Default")
      (node (ref "IC8") (pin "13") (pinfunction "13_13") (pintype "no_connect"))
    )
    (net (code "90") (name "unconnected-(IC8-Pad15)") (class "Default")
      (node (ref "IC8") (pin "15") (pinfunction "15_15") (pintype "no_connect"))
    )
    (net (code "91") (name "unconnected-(IC8-Pad16)") (class "Default")
      (node (ref "IC8") (pin "16") (pinfunction "16_16") (pintype "no_connect"))
    )
    (net (code "92") (name "unconnected-(IC8-Pad17)") (class "Default")
      (node (ref "IC8") (pin "17") (pinfunction "17_17") (pintype "no_connect"))
    )
    (net (code "93") (name "unconnected-(IC8-Pad18)") (class "Default")
      (node (ref "IC8") (pin "18") (pinfunction "18_18") (pintype "no_connect"))
    )
  )
)
